# Cansat2019_1516_Container_v05.net
KiCad netlist of a schematic drawn in EAGLE
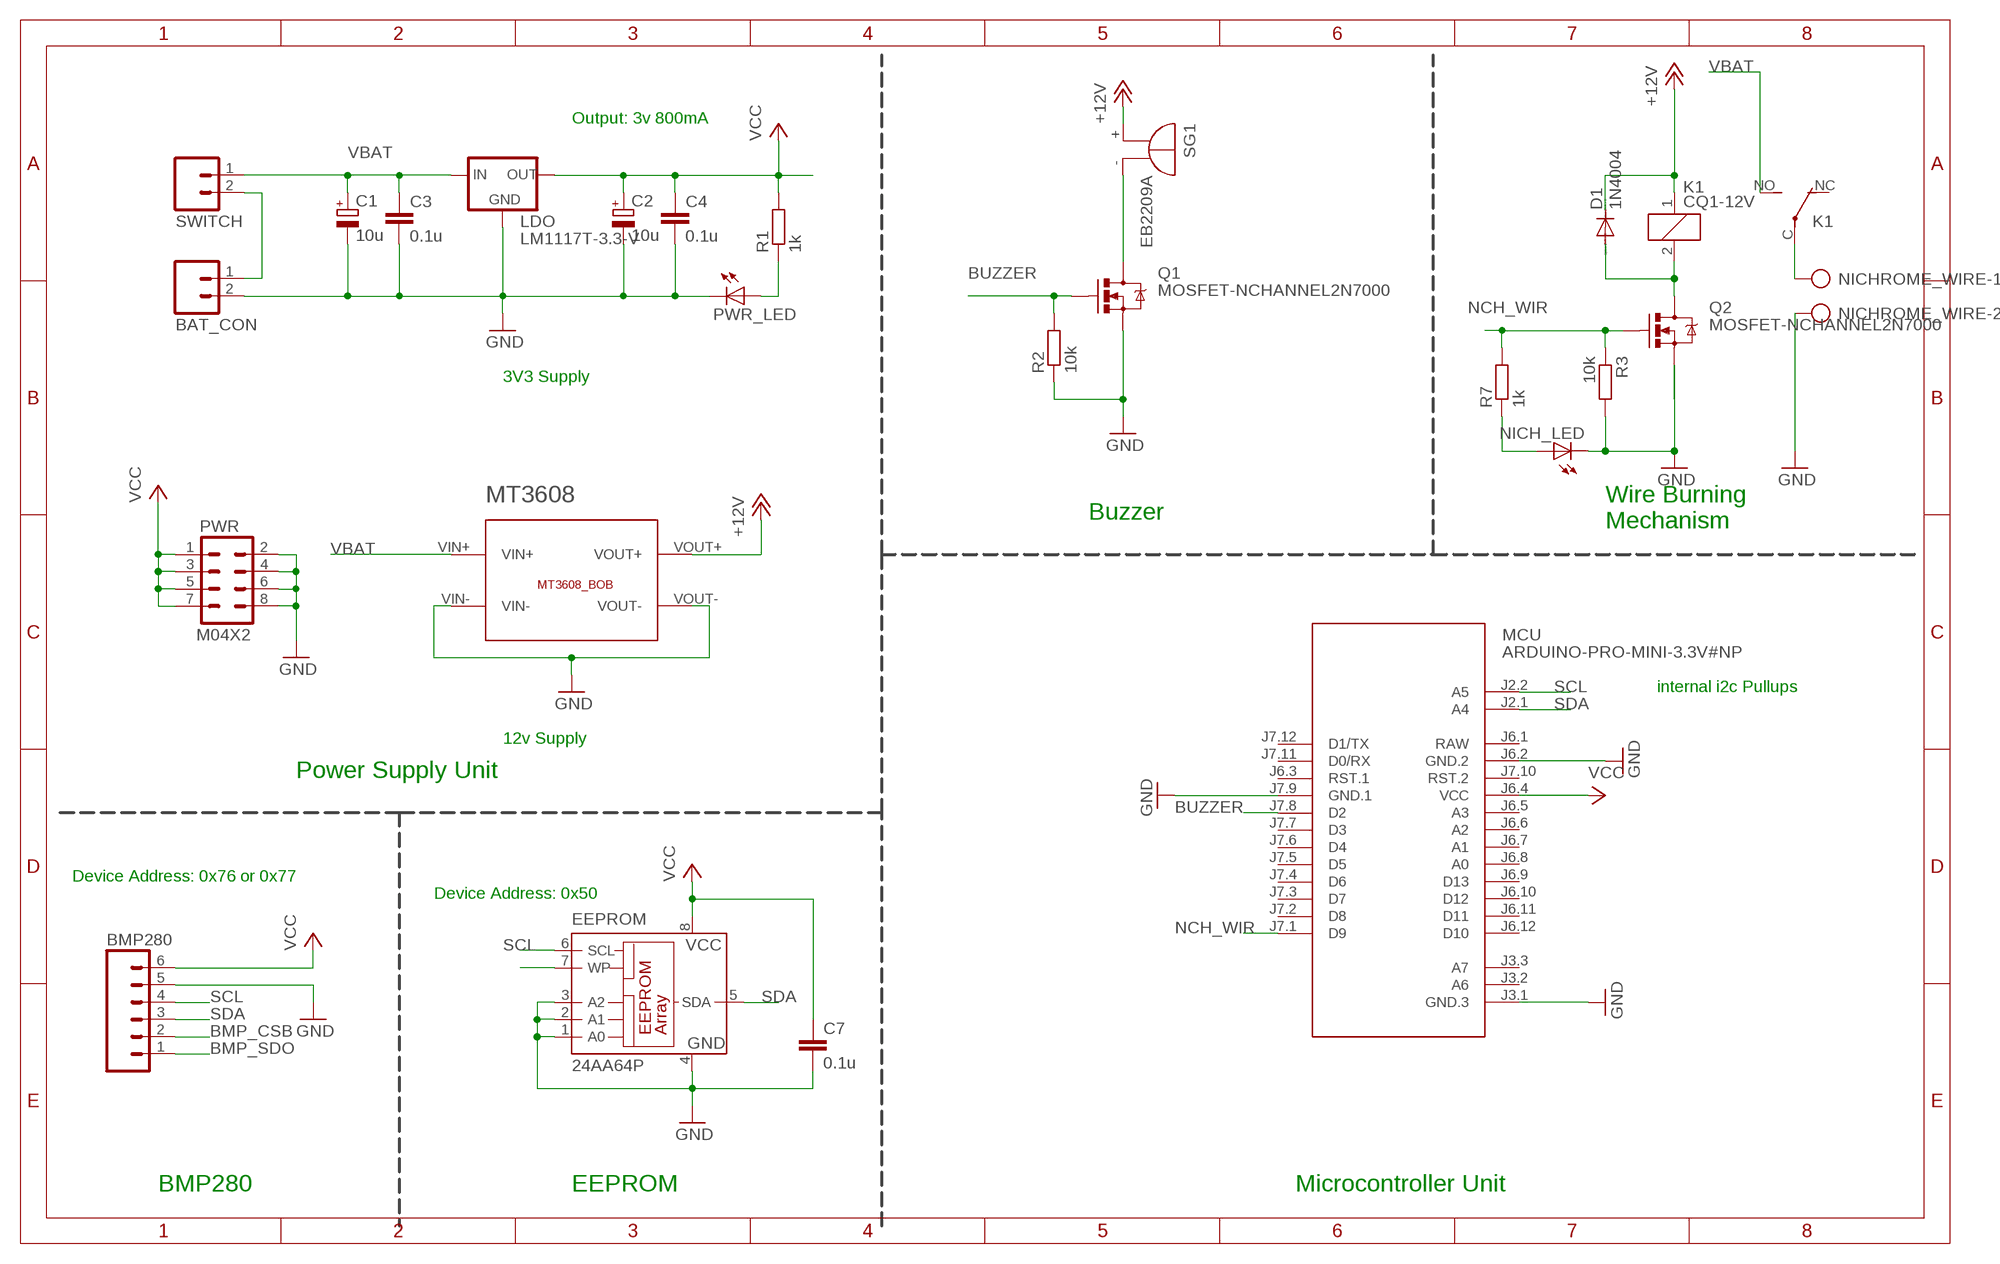
[diagram p0: schematic, sheet 1]

(export (version "E")
  (design (tool "Eeschema 10.0.6"))
  (components
    (comp (ref "BAT_CON")
      (value "M02")
      (footprint "eagle-import:02P")
      (libsource (lib "eagle-import") (part "M02"))
    )
    (comp (ref "BMP280")
      (value "M06")
      (footprint "eagle-import:06P")
      (libsource (lib "eagle-import") (part "M06"))
    )
    (comp (ref "C1")
      (value "10u")
      (footprint "eagle-import:E2,5-6")
      (libsource (lib "eagle-import") (part "CPOL-EUE2.5-6"))
    )
    (comp (ref "C2")
      (value "10u")
      (footprint "eagle-import:E2,5-6")
      (libsource (lib "eagle-import") (part "CPOL-EUE2.5-6"))
    )
    (comp (ref "C3")
      (value "0.1u")
      (footprint "eagle-import:C025-025X050")
      (libsource (lib "eagle-import") (part "C-EU025-025X050"))
    )
    (comp (ref "C4")
      (value "0.1u")
      (footprint "eagle-import:C025-025X050")
      (libsource (lib "eagle-import") (part "C-EU025-025X050"))
    )
    (comp (ref "C7")
      (value "0.1u")
      (footprint "eagle-import:C025-025X050")
      (libsource (lib "eagle-import") (part "C-EU025-025X050"))
    )
    (comp (ref "D1")
      (value "1N4004")
      (footprint "eagle-import:DO41-10")
      (libsource (lib "eagle-import") (part "1N4004"))
    )
    (comp (ref "EEPROM")
      (value "24AA64P")
      (footprint "eagle-import:DIL8")
      (fields (field (name "MF") "MICROCHIP") (field (name "MPN") "24AA64-I/P"))
      (libsource (lib "eagle-import") (part "24PAA64"))
    )
    (comp (ref "K1")
      (value "CQ1-12V")
      (footprint "eagle-import:CQ1")
      (libsource (lib "eagle-import") (part "CQ1-12V"))
    )
    (comp (ref "LDO")
      (value "LM1117T-3.3-V")
      (footprint "eagle-import:TO220V")
      (libsource (lib "eagle-import") (part "LM1117T--V3.3"))
    )
    (comp (ref "MCU")
      (value "ARDUINO-PRO-MINI-3.3V#NP")
      (footprint "eagle-import:ARDUINO-PRO-MINI#NP")
      (libsource (lib "eagle-import") (part "ARDUINO-PRO-MINI-#NP3.3V"))
    )
    (comp (ref "MT3608")
      (value "MT3608_BOB")
      (footprint "eagle-import:MT3608_BOB")
      (libsource (lib "eagle-import") (part "MT3608_BOB"))
    )
    (comp (ref "NICHROME_WIRE")
      (value "AK500/2-H")
      (footprint "eagle-import:AK500_2-H")
      (libsource (lib "eagle-import") (part "AK500/2-H"))
    )
    (comp (ref "NICH_LED")
      (value "LED3MM")
      (footprint "eagle-import:LED3MM")
      (libsource (lib "eagle-import") (part "LED3MM"))
    )
    (comp (ref "PWR")
      (value "M04X2")
      (footprint "eagle-import:2X4")
      (libsource (lib "eagle-import") (part "M04X2"))
    )
    (comp (ref "PWR_LED")
      (value "LED3MM")
      (footprint "eagle-import:LED3MM")
      (libsource (lib "eagle-import") (part "LED3MM"))
    )
    (comp (ref "Q1")
      (value "MOSFET-NCHANNEL2N7000")
      (footprint "eagle-import:TO-92")
      (libsource (lib "eagle-import") (part "MOSFET-NCHANNEL2N7000"))
    )
    (comp (ref "Q2")
      (value "MOSFET-NCHANNEL2N7000")
      (footprint "eagle-import:TO-92")
      (libsource (lib "eagle-import") (part "MOSFET-NCHANNEL2N7000"))
    )
    (comp (ref "R1")
      (value "1k")
      (footprint "eagle-import:0204_7")
      (libsource (lib "eagle-import") (part "R-EU_0204/7"))
    )
    (comp (ref "R2")
      (value "10k")
      (footprint "eagle-import:0204_7")
      (libsource (lib "eagle-import") (part "R-EU_0204/7"))
    )
    (comp (ref "R3")
      (value "10k")
      (footprint "eagle-import:0204_7")
      (libsource (lib "eagle-import") (part "R-EU_0204/7"))
    )
    (comp (ref "R7")
      (value "1k")
      (footprint "eagle-import:0204_7")
      (libsource (lib "eagle-import") (part "R-EU_0204/7"))
    )
    (comp (ref "SG1")
      (value "EB2209A")
      (footprint "eagle-import:EB2209A")
      (libsource (lib "eagle-import") (part "EB2209A"))
    )
    (comp (ref "SWITCH")
      (value "M02")
      (footprint "eagle-import:02P")
      (libsource (lib "eagle-import") (part "M02"))
    )
  )
  (nets
    (net (code "1") (name "+12V") (class "Default")
      (node (ref "D1") (pin "C") (pinfunction "C_C") (pintype "passive"))
      (node (ref "K1") (pin "1") (pinfunction "1_1") (pintype "passive"))
      (node (ref "MT3608") (pin "VOUT+") (pinfunction "VOUT+_VOUT+") (pintype "bidirectional"))
      (node (ref "SG1") (pin "+") (pinfunction "+_+") (pintype "passive"))
    )
    (net (code "2") (name "/BMP_CSB") (class "Default")
      (node (ref "BMP280") (pin "2") (pinfunction "2_2") (pintype "passive"))
    )
    (net (code "3") (name "/BMP_SDO") (class "Default")
      (node (ref "BMP280") (pin "1") (pinfunction "1_1") (pintype "passive"))
    )
    (net (code "4") (name "/BUZZER") (class "Default")
      (node (ref "MCU") (pin "J7.8") (pinfunction "D2_J7.8") (pintype "bidirectional"))
      (node (ref "Q1") (pin "2") (pinfunction "G_2") (pintype "passive"))
      (node (ref "R2") (pin "2") (pinfunction "2_2") (pintype "passive"))
    )
    (net (code "5") (name "/NCH_WIR") (class "Default")
      (node (ref "MCU") (pin "J7.1") (pinfunction "D9_J7.1") (pintype "bidirectional"))
      (node (ref "Q2") (pin "2") (pinfunction "G_2") (pintype "passive"))
      (node (ref "R3") (pin "1") (pinfunction "1_1") (pintype "passive"))
      (node (ref "R7") (pin "2") (pinfunction "2_2") (pintype "passive"))
    )
    (net (code "6") (name "/RAW") (class "Default")
      (node (ref "MCU") (pin "J6.1") (pinfunction "RAW_J6.1") (pintype "power_in"))
    )
    (net (code "7") (name "/SCL") (class "Default")
      (node (ref "BMP280") (pin "4") (pinfunction "4_4") (pintype "passive"))
      (node (ref "EEPROM") (pin "6") (pinfunction "SCL_6") (pintype "input"))
      (node (ref "MCU") (pin "J2.2") (pinfunction "A5_J2.2") (pintype "bidirectional"))
    )
    (net (code "8") (name "/SDA") (class "Default")
      (node (ref "BMP280") (pin "3") (pinfunction "3_3") (pintype "passive"))
      (node (ref "EEPROM") (pin "5") (pinfunction "SDA_5") (pintype "bidirectional"))
      (node (ref "MCU") (pin "J2.1") (pinfunction "A4_J2.1") (pintype "bidirectional"))
    )
    (net (code "9") (name "/VBAT") (class "Default")
      (node (ref "C1") (pin "+") (pinfunction "+_+") (pintype "passive"))
      (node (ref "C3") (pin "1") (pinfunction "1_1") (pintype "passive"))
      (node (ref "K1") (pin "NO") (pinfunction "S_NO") (pintype "passive"))
      (node (ref "LDO") (pin "3") (pinfunction "IN_3") (pintype "input"))
      (node (ref "MT3608") (pin "VIN+") (pinfunction "VIN+_VIN+") (pintype "bidirectional"))
      (node (ref "SWITCH") (pin "1") (pinfunction "1_1") (pintype "passive"))
    )
    (net (code "10") (name "GND") (class "Default")
      (node (ref "BAT_CON") (pin "2") (pinfunction "2_2") (pintype "passive"))
      (node (ref "BMP280") (pin "5") (pinfunction "5_5") (pintype "passive"))
      (node (ref "C1") (pin "-") (pinfunction "-_-") (pintype "passive"))
      (node (ref "C2") (pin "-") (pinfunction "-_-") (pintype "passive"))
      (node (ref "C3") (pin "2") (pinfunction "2_2") (pintype "passive"))
      (node (ref "C4") (pin "2") (pinfunction "2_2") (pintype "passive"))
      (node (ref "C7") (pin "2") (pinfunction "2_2") (pintype "passive"))
      (node (ref "EEPROM") (pin "1") (pinfunction "A0_1") (pintype "input"))
      (node (ref "EEPROM") (pin "2") (pinfunction "A1_2") (pintype "input"))
      (node (ref "EEPROM") (pin "3") (pinfunction "A2_3") (pintype "input"))
      (node (ref "EEPROM") (pin "4") (pinfunction "GND_4") (pintype "power_in"))
      (node (ref "LDO") (pin "1") (pinfunction "GND_1") (pintype "input"))
      (node (ref "MCU") (pin "J3.1") (pinfunction "GND.3_J3.1") (pintype "bidirectional"))
      (node (ref "MCU") (pin "J6.2") (pinfunction "GND.2_J6.2") (pintype "power_in"))
      (node (ref "MCU") (pin "J7.9") (pinfunction "GND.1_J7.9") (pintype "power_in"))
      (node (ref "MT3608") (pin "VIN-") (pinfunction "VIN-_VIN-") (pintype "bidirectional"))
      (node (ref "MT3608") (pin "VOUT-") (pinfunction "VOUT-_VOUT-") (pintype "bidirectional"))
      (node (ref "NICHROME_WIRE") (pin "2") (pinfunction "KL_2") (pintype "passive"))
      (node (ref "NICH_LED") (pin "K") (pinfunction "C_K") (pintype "passive"))
      (node (ref "PWR") (pin "2") (pinfunction "2_2") (pintype "passive"))
      (node (ref "PWR") (pin "4") (pinfunction "4_4") (pintype "passive"))
      (node (ref "PWR") (pin "6") (pinfunction "6_6") (pintype "passive"))
      (node (ref "PWR") (pin "8") (pinfunction "8_8") (pintype "passive"))
      (node (ref "PWR_LED") (pin "K") (pinfunction "C_K") (pintype "passive"))
      (node (ref "Q1") (pin "1") (pinfunction "S_1") (pintype "passive"))
      (node (ref "Q2") (pin "1") (pinfunction "S_1") (pintype "passive"))
      (node (ref "R2") (pin "1") (pinfunction "1_1") (pintype "passive"))
      (node (ref "R3") (pin "2") (pinfunction "2_2") (pintype "passive"))
    )
    (net (code "11") (name "Net-(BAT_CON-Pad1)") (class "Default")
      (node (ref "BAT_CON") (pin "1") (pinfunction "1_1") (pintype "passive"))
      (node (ref "SWITCH") (pin "2") (pinfunction "2_2") (pintype "passive"))
    )
    (net (code "12") (name "Net-(K1B-P)") (class "Default")
      (node (ref "K1") (pin "C") (pinfunction "P_C") (pintype "passive"))
      (node (ref "NICHROME_WIRE") (pin "1") (pinfunction "KL_1") (pintype "passive"))
    )
    (net (code "13") (name "Net-(NICH_LED-PadA)") (class "Default")
      (node (ref "NICH_LED") (pin "A") (pinfunction "A_A") (pintype "passive"))
      (node (ref "R7") (pin "1") (pinfunction "1_1") (pintype "passive"))
    )
    (net (code "14") (name "Net-(PWR_LED-PadA)") (class "Default")
      (node (ref "PWR_LED") (pin "A") (pinfunction "A_A") (pintype "passive"))
      (node (ref "R1") (pin "1") (pinfunction "1_1") (pintype "passive"))
    )
    (net (code "15") (name "Net-(Q1-D)") (class "Default")
      (node (ref "Q1") (pin "3") (pinfunction "D_3") (pintype "passive"))
      (node (ref "SG1") (pin "-") (pinfunction "-_-") (pintype "passive"))
    )
    (net (code "16") (name "Net-(Q2-D)") (class "Default")
      (node (ref "D1") (pin "A") (pinfunction "A_A") (pintype "passive"))
      (node (ref "K1") (pin "2") (pinfunction "2_2") (pintype "passive"))
      (node (ref "Q2") (pin "3") (pinfunction "D_3") (pintype "passive"))
    )
    (net (code "17") (name "VCC") (class "Default")
      (node (ref "BMP280") (pin "6") (pinfunction "6_6") (pintype "passive"))
      (node (ref "C2") (pin "+") (pinfunction "+_+") (pintype "passive"))
      (node (ref "C4") (pin "1") (pinfunction "1_1") (pintype "passive"))
      (node (ref "C7") (pin "1") (pinfunction "1_1") (pintype "passive"))
      (node (ref "EEPROM") (pin "8") (pinfunction "VCC_8") (pintype "power_in"))
      (node (ref "LDO") (pin "2") (pinfunction "OUT_2") (pintype "passive"))
      (node (ref "MCU") (pin "J6.4") (pinfunction "VCC_J6.4") (pintype "power_in"))
      (node (ref "PWR") (pin "1") (pinfunction "1_1") (pintype "passive"))
      (node (ref "PWR") (pin "3") (pinfunction "3_3") (pintype "passive"))
      (node (ref "PWR") (pin "5") (pinfunction "5_5") (pintype "passive"))
      (node (ref "PWR") (pin "7") (pinfunction "7_7") (pintype "passive"))
      (node (ref "R1") (pin "2") (pinfunction "2_2") (pintype "passive"))
    )
    (net (code "18") (name "unconnected-(EEPROM-WP-Pad7)") (class "Default")
      (node (ref "EEPROM") (pin "7") (pinfunction "WP_7") (pintype "input"))
    )
    (net (code "19") (name "unconnected-(K1B-O-PadNC)") (class "Default")
      (node (ref "K1") (pin "NC") (pinfunction "O_NC") (pintype "passive"))
    )
    (net (code "20") (name "unconnected-(MCU-A0-PadJ6.8)") (class "Default")
      (node (ref "MCU") (pin "J6.8") (pinfunction "A0_J6.8") (pintype "bidirectional"))
    )
    (net (code "21") (name "unconnected-(MCU-A1-PadJ6.7)") (class "Default")
      (node (ref "MCU") (pin "J6.7") (pinfunction "A1_J6.7") (pintype "bidirectional"))
    )
    (net (code "22") (name "unconnected-(MCU-A2-PadJ6.6)") (class "Default")
      (node (ref "MCU") (pin "J6.6") (pinfunction "A2_J6.6") (pintype "bidirectional"))
    )
    (net (code "23") (name "unconnected-(MCU-A3-PadJ6.5)") (class "Default")
      (node (ref "MCU") (pin "J6.5") (pinfunction "A3_J6.5") (pintype "bidirectional"))
    )
    (net (code "24") (name "unconnected-(MCU-A6-PadJ3.2)") (class "Default")
      (node (ref "MCU") (pin "J3.2") (pinfunction "A6_J3.2") (pintype "bidirectional"))
    )
    (net (code "25") (name "unconnected-(MCU-A7-PadJ3.3)") (class "Default")
      (node (ref "MCU") (pin "J3.3") (pinfunction "A7_J3.3") (pintype "bidirectional"))
    )
    (net (code "26") (name "unconnected-(MCU-D0{slash}RX-PadJ7.11)") (class "Default")
      (node (ref "MCU") (pin "J7.11") (pinfunction "D0/RX_J7.11") (pintype "bidirectional"))
    )
    (net (code "27") (name "unconnected-(MCU-D1{slash}TX-PadJ7.12)") (class "Default")
      (node (ref "MCU") (pin "J7.12") (pinfunction "D1/TX_J7.12") (pintype "bidirectional"))
    )
    (net (code "28") (name "unconnected-(MCU-D3-PadJ7.7)") (class "Default")
      (node (ref "MCU") (pin "J7.7") (pinfunction "D3_J7.7") (pintype "bidirectional"))
    )
    (net (code "29") (name "unconnected-(MCU-D4-PadJ7.6)") (class "Default")
      (node (ref "MCU") (pin "J7.6") (pinfunction "D4_J7.6") (pintype "bidirectional"))
    )
    (net (code "30") (name "unconnected-(MCU-D5-PadJ7.5)") (class "Default")
      (node (ref "MCU") (pin "J7.5") (pinfunction "D5_J7.5") (pintype "bidirectional"))
    )
    (net (code "31") (name "unconnected-(MCU-D6-PadJ7.4)") (class "Default")
      (node (ref "MCU") (pin "J7.4") (pinfunction "D6_J7.4") (pintype "bidirectional"))
    )
    (net (code "32") (name "unconnected-(MCU-D7-PadJ7.3)") (class "Default")
      (node (ref "MCU") (pin "J7.3") (pinfunction "D7_J7.3") (pintype "bidirectional"))
    )
    (net (code "33") (name "unconnected-(MCU-D8-PadJ7.2)") (class "Default")
      (node (ref "MCU") (pin "J7.2") (pinfunction "D8_J7.2") (pintype "bidirectional"))
    )
    (net (code "34") (name "unconnected-(MCU-D10-PadJ6.12)") (class "Default")
      (node (ref "MCU") (pin "J6.12") (pinfunction "D10_J6.12") (pintype "bidirectional"))
    )
    (net (code "35") (name "unconnected-(MCU-D11-PadJ6.11)") (class "Default")
      (node (ref "MCU") (pin "J6.11") (pinfunction "D11_J6.11") (pintype "bidirectional"))
    )
    (net (code "36") (name "unconnected-(MCU-D12-PadJ6.10)") (class "Default")
      (node (ref "MCU") (pin "J6.10") (pinfunction "D12_J6.10") (pintype "bidirectional"))
    )
    (net (code "37") (name "unconnected-(MCU-D13-PadJ6.9)") (class "Default")
      (node (ref "MCU") (pin "J6.9") (pinfunction "D13_J6.9") (pintype "bidirectional"))
    )
    (net (code "38") (name "unconnected-(MCU-RST.1-PadJ6.3)") (class "Default")
      (node (ref "MCU") (pin "J6.3") (pinfunction "RST.1_J6.3") (pintype "bidirectional"))
    )
    (net (code "39") (name "unconnected-(MCU-RST.2-PadJ7.10)") (class "Default")
      (node (ref "MCU") (pin "J7.10") (pinfunction "RST.2_J7.10") (pintype "bidirectional"))
    )
  )
)
